# C64-Wifi_UserP.net
KiCad netlist of a schematic drawn in EAGLE
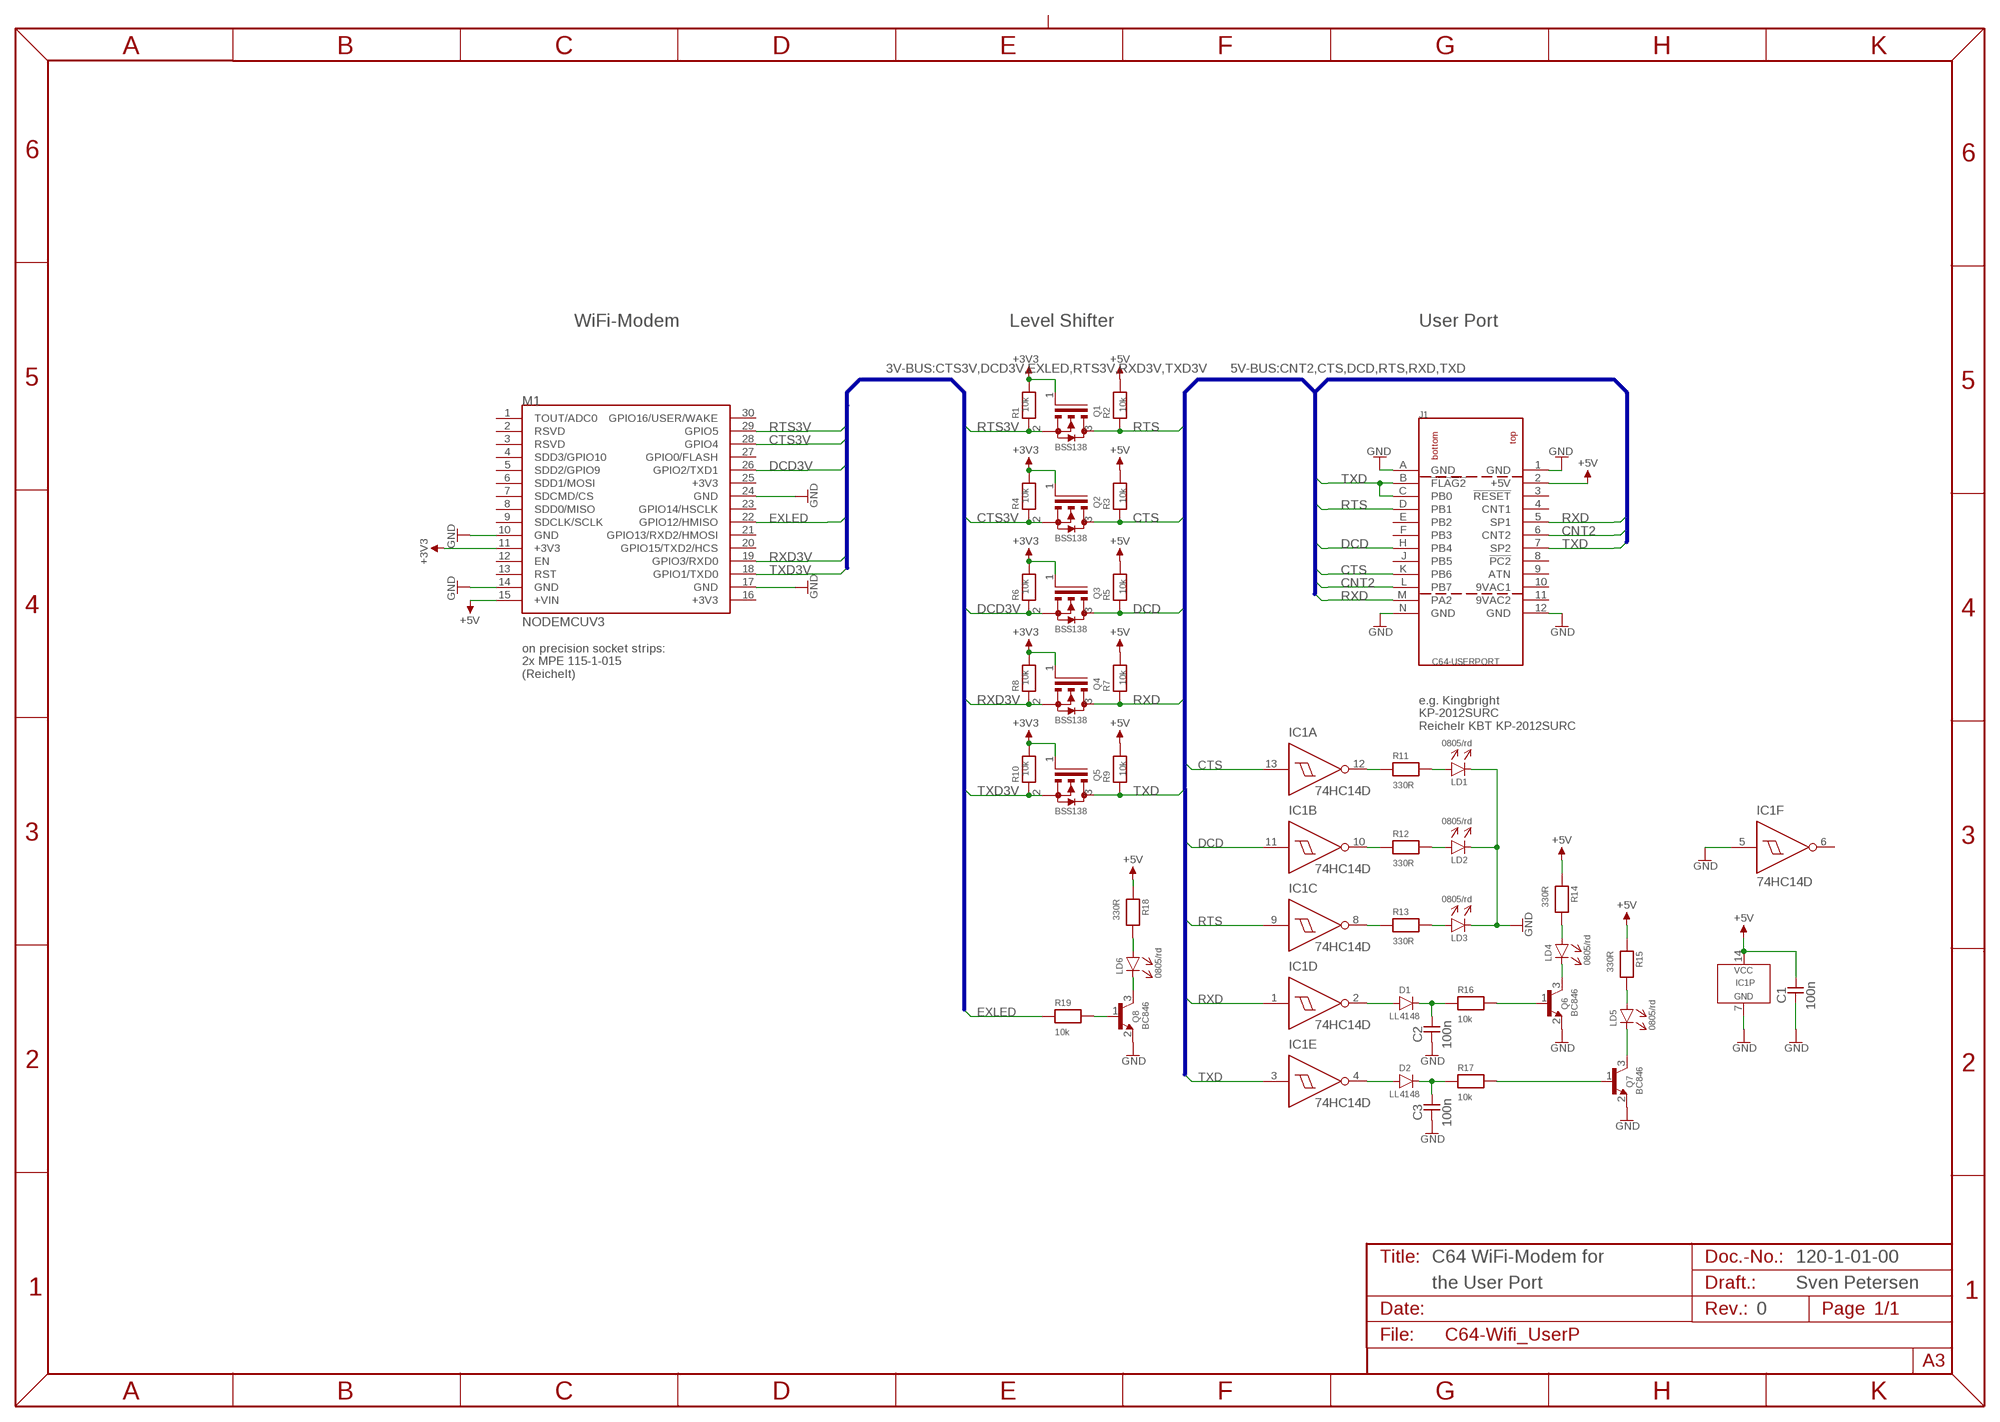
[diagram p0: schematic, sheet 1]

(export (version "E")
  (design (tool "Eeschema 10.0.6"))
  (components
    (comp (ref "C1")
      (value "100n")
      (footprint "eagle-import:0805")
      (libsource (lib "eagle-import") (part "C-0805"))
    )
    (comp (ref "C2")
      (value "100n")
      (footprint "eagle-import:0805")
      (libsource (lib "eagle-import") (part "C-0805"))
    )
    (comp (ref "C3")
      (value "100n")
      (footprint "eagle-import:0805")
      (libsource (lib "eagle-import") (part "C-0805"))
    )
    (comp (ref "D1")
      (value "LL4148")
      (footprint "eagle-import:SOD80C")
      (libsource (lib "eagle-import") (part "LL4148"))
    )
    (comp (ref "D2")
      (value "LL4148")
      (footprint "eagle-import:SOD80C")
      (libsource (lib "eagle-import") (part "LL4148"))
    )
    (comp (ref "IC1")
      (value "74HC14D")
      (footprint "eagle-import:SO-14")
      (libsource (lib "eagle-import") (part "7414"))
    )
    (comp (ref "J1")
      (value "C64-USERPORT")
      (footprint "eagle-import:USERPORT")
      (libsource (lib "eagle-import") (part "C64-USERPORT"))
    )
    (comp (ref "LD1")
      (value "0805/rd")
      (footprint "eagle-import:0805")
      (libsource (lib "eagle-import") (part "0805-LED"))
    )
    (comp (ref "LD2")
      (value "0805/rd")
      (footprint "eagle-import:0805")
      (libsource (lib "eagle-import") (part "0805-LED"))
    )
    (comp (ref "LD3")
      (value "0805/rd")
      (footprint "eagle-import:0805")
      (libsource (lib "eagle-import") (part "0805-LED"))
    )
    (comp (ref "LD4")
      (value "0805/rd")
      (footprint "eagle-import:0805")
      (libsource (lib "eagle-import") (part "0805-LED"))
    )
    (comp (ref "LD5")
      (value "0805/rd")
      (footprint "eagle-import:0805")
      (libsource (lib "eagle-import") (part "0805-LED"))
    )
    (comp (ref "LD6")
      (value "0805/rd")
      (footprint "eagle-import:0805")
      (libsource (lib "eagle-import") (part "0805-LED"))
    )
    (comp (ref "M1")
      (value "NODEMCUV3")
      (footprint "eagle-import:NODEMCUV3")
      (libsource (lib "eagle-import") (part "NODEMCUV3"))
    )
    (comp (ref "Q1")
      (value "BSS138")
      (footprint "eagle-import:SOT23")
      (libsource (lib "eagle-import") (part "BSS138"))
    )
    (comp (ref "Q2")
      (value "BSS138")
      (footprint "eagle-import:SOT23")
      (libsource (lib "eagle-import") (part "BSS138"))
    )
    (comp (ref "Q3")
      (value "BSS138")
      (footprint "eagle-import:SOT23")
      (libsource (lib "eagle-import") (part "BSS138"))
    )
    (comp (ref "Q4")
      (value "BSS138")
      (footprint "eagle-import:SOT23")
      (libsource (lib "eagle-import") (part "BSS138"))
    )
    (comp (ref "Q5")
      (value "BSS138")
      (footprint "eagle-import:SOT23")
      (libsource (lib "eagle-import") (part "BSS138"))
    )
    (comp (ref "Q6")
      (value "BC846")
      (footprint "eagle-import:SOT23")
      (libsource (lib "eagle-import") (part "BC846"))
    )
    (comp (ref "Q7")
      (value "BC846")
      (footprint "eagle-import:SOT23")
      (libsource (lib "eagle-import") (part "BC846"))
    )
    (comp (ref "Q8")
      (value "BC846")
      (footprint "eagle-import:SOT23")
      (libsource (lib "eagle-import") (part "BC846"))
    )
    (comp (ref "R1")
      (value "10k")
      (footprint "eagle-import:0805")
      (libsource (lib "eagle-import") (part "R-0805"))
    )
    (comp (ref "R2")
      (value "10k")
      (footprint "eagle-import:0805")
      (libsource (lib "eagle-import") (part "R-0805"))
    )
    (comp (ref "R3")
      (value "10k")
      (footprint "eagle-import:0805")
      (libsource (lib "eagle-import") (part "R-0805"))
    )
    (comp (ref "R4")
      (value "10k")
      (footprint "eagle-import:0805")
      (libsource (lib "eagle-import") (part "R-0805"))
    )
    (comp (ref "R5")
      (value "10k")
      (footprint "eagle-import:0805")
      (libsource (lib "eagle-import") (part "R-0805"))
    )
    (comp (ref "R6")
      (value "10k")
      (footprint "eagle-import:0805")
      (libsource (lib "eagle-import") (part "R-0805"))
    )
    (comp (ref "R7")
      (value "10k")
      (footprint "eagle-import:0805")
      (libsource (lib "eagle-import") (part "R-0805"))
    )
    (comp (ref "R8")
      (value "10k")
      (footprint "eagle-import:0805")
      (libsource (lib "eagle-import") (part "R-0805"))
    )
    (comp (ref "R9")
      (value "10k")
      (footprint "eagle-import:0805")
      (libsource (lib "eagle-import") (part "R-0805"))
    )
    (comp (ref "R10")
      (value "10k")
      (footprint "eagle-import:0805")
      (libsource (lib "eagle-import") (part "R-0805"))
    )
    (comp (ref "R11")
      (value "330R")
      (footprint "eagle-import:0805")
      (libsource (lib "eagle-import") (part "R-0805"))
    )
    (comp (ref "R12")
      (value "330R")
      (footprint "eagle-import:0805")
      (libsource (lib "eagle-import") (part "R-0805"))
    )
    (comp (ref "R13")
      (value "330R")
      (footprint "eagle-import:0805")
      (libsource (lib "eagle-import") (part "R-0805"))
    )
    (comp (ref "R14")
      (value "330R")
      (footprint "eagle-import:0805")
      (libsource (lib "eagle-import") (part "R-0805"))
    )
    (comp (ref "R15")
      (value "330R")
      (footprint "eagle-import:0805")
      (libsource (lib "eagle-import") (part "R-0805"))
    )
    (comp (ref "R16")
      (value "10k")
      (footprint "eagle-import:0805")
      (libsource (lib "eagle-import") (part "R-0805"))
    )
    (comp (ref "R17")
      (value "10k")
      (footprint "eagle-import:0805")
      (libsource (lib "eagle-import") (part "R-0805"))
    )
    (comp (ref "R18")
      (value "330R")
      (footprint "eagle-import:0805")
      (libsource (lib "eagle-import") (part "R-0805"))
    )
    (comp (ref "R19")
      (value "10k")
      (footprint "eagle-import:0805")
      (libsource (lib "eagle-import") (part "R-0805"))
    )
  )
  (nets
    (net (code "3") (name "+3V3") (class "Default")
      (node (ref "M1") (pin "11") (pinfunction "+3V3_11") (pintype "bidirectional"))
      (node (ref "Q1") (pin "1") (pinfunction "G_1") (pintype "bidirectional"))
      (node (ref "Q2") (pin "1") (pinfunction "G_1") (pintype "bidirectional"))
      (node (ref "Q3") (pin "1") (pinfunction "G_1") (pintype "bidirectional"))
      (node (ref "Q4") (pin "1") (pinfunction "G_1") (pintype "bidirectional"))
      (node (ref "Q5") (pin "1") (pinfunction "G_1") (pintype "bidirectional"))
      (node (ref "R1") (pin "2") (pinfunction "2_2") (pintype "passive"))
      (node (ref "R10") (pin "2") (pinfunction "2_2") (pintype "passive"))
      (node (ref "R4") (pin "2") (pinfunction "2_2") (pintype "passive"))
      (node (ref "R6") (pin "2") (pinfunction "2_2") (pintype "passive"))
      (node (ref "R8") (pin "2") (pinfunction "2_2") (pintype "passive"))
    )
    (net (code "4") (name "+5V") (class "Default")
      (node (ref "C1") (pin "2") (pinfunction "2_2") (pintype "passive"))
      (node (ref "IC1") (pin "14") (pinfunction "VCC_14") (pintype "bidirectional"))
      (node (ref "J1") (pin "2") (pinfunction "+5V_2") (pintype "power_in"))
      (node (ref "M1") (pin "15") (pinfunction "+VIN_15") (pintype "bidirectional"))
      (node (ref "R14") (pin "1") (pinfunction "1_1") (pintype "passive"))
      (node (ref "R15") (pin "1") (pinfunction "1_1") (pintype "passive"))
      (node (ref "R18") (pin "1") (pinfunction "1_1") (pintype "passive"))
      (node (ref "R2") (pin "2") (pinfunction "2_2") (pintype "passive"))
      (node (ref "R3") (pin "2") (pinfunction "2_2") (pintype "passive"))
      (node (ref "R5") (pin "2") (pinfunction "2_2") (pintype "passive"))
      (node (ref "R7") (pin "2") (pinfunction "2_2") (pintype "passive"))
      (node (ref "R9") (pin "2") (pinfunction "2_2") (pintype "passive"))
    )
    (net (code "5") (name "/9VAC1") (class "Default")
      (node (ref "J1") (pin "10") (pinfunction "9VAC1_10") (pintype "power_in"))
    )
    (net (code "6") (name "/9VAC2") (class "Default")
      (node (ref "J1") (pin "11") (pinfunction "9VAC2_11") (pintype "power_in"))
    )
    (net (code "7") (name "/CNT2") (class "Default")
      (node (ref "J1") (pin "6") (pinfunction "CNT2_6") (pintype "input"))
      (node (ref "J1") (pin "L") (pinfunction "PB7_L") (pintype "bidirectional"))
    )
    (net (code "8") (name "/CTS") (class "Default")
      (node (ref "IC1") (pin "13") (pinfunction "I_13") (pintype "input"))
      (node (ref "J1") (pin "K") (pinfunction "PB6_K") (pintype "bidirectional"))
      (node (ref "Q2") (pin "3") (pinfunction "D_3") (pintype "bidirectional"))
      (node (ref "R3") (pin "1") (pinfunction "1_1") (pintype "passive"))
    )
    (net (code "9") (name "/CTS3V") (class "Default")
      (node (ref "M1") (pin "28") (pinfunction "GPIO4_28") (pintype "bidirectional"))
      (node (ref "Q2") (pin "2") (pinfunction "S_2") (pintype "bidirectional"))
      (node (ref "R4") (pin "1") (pinfunction "1_1") (pintype "passive"))
    )
    (net (code "10") (name "/DCD") (class "Default")
      (node (ref "IC1") (pin "11") (pinfunction "I_11") (pintype "input"))
      (node (ref "J1") (pin "H") (pinfunction "PB4_H") (pintype "bidirectional"))
      (node (ref "Q3") (pin "3") (pinfunction "D_3") (pintype "bidirectional"))
      (node (ref "R5") (pin "1") (pinfunction "1_1") (pintype "passive"))
    )
    (net (code "11") (name "/DCD3V") (class "Default")
      (node (ref "M1") (pin "26") (pinfunction "GPIO2/TXD1_26") (pintype "bidirectional"))
      (node (ref "Q3") (pin "2") (pinfunction "S_2") (pintype "bidirectional"))
      (node (ref "R6") (pin "1") (pinfunction "1_1") (pintype "passive"))
    )
    (net (code "12") (name "/EXLED") (class "Default")
      (node (ref "M1") (pin "22") (pinfunction "GPIO12/HMISO_22") (pintype "bidirectional"))
      (node (ref "R19") (pin "1") (pinfunction "1_1") (pintype "passive"))
    )
    (net (code "13") (name "/RTS") (class "Default")
      (node (ref "IC1") (pin "9") (pinfunction "I_9") (pintype "input"))
      (node (ref "J1") (pin "D") (pinfunction "PB1_D") (pintype "bidirectional"))
      (node (ref "Q1") (pin "3") (pinfunction "D_3") (pintype "bidirectional"))
      (node (ref "R2") (pin "1") (pinfunction "1_1") (pintype "passive"))
    )
    (net (code "14") (name "/RTS3V") (class "Default")
      (node (ref "M1") (pin "29") (pinfunction "GPIO5_29") (pintype "bidirectional"))
      (node (ref "Q1") (pin "2") (pinfunction "S_2") (pintype "bidirectional"))
      (node (ref "R1") (pin "1") (pinfunction "1_1") (pintype "passive"))
    )
    (net (code "15") (name "/RXD") (class "Default")
      (node (ref "IC1") (pin "1") (pinfunction "I_1") (pintype "input"))
      (node (ref "J1") (pin "5") (pinfunction "SP1_5") (pintype "bidirectional"))
      (node (ref "J1") (pin "M") (pinfunction "PA2_M") (pintype "bidirectional"))
      (node (ref "Q4") (pin "3") (pinfunction "D_3") (pintype "bidirectional"))
      (node (ref "R7") (pin "1") (pinfunction "1_1") (pintype "passive"))
    )
    (net (code "16") (name "/RXD3V") (class "Default")
      (node (ref "M1") (pin "19") (pinfunction "GPIO3/RXD0_19") (pintype "bidirectional"))
      (node (ref "Q4") (pin "2") (pinfunction "S_2") (pintype "bidirectional"))
      (node (ref "R8") (pin "1") (pinfunction "1_1") (pintype "passive"))
    )
    (net (code "17") (name "/TXD") (class "Default")
      (node (ref "IC1") (pin "3") (pinfunction "I_3") (pintype "input"))
      (node (ref "J1") (pin "7") (pinfunction "SP2_7") (pintype "bidirectional"))
      (node (ref "J1") (pin "B") (pinfunction "~{FLAG2}_B") (pintype "input"))
      (node (ref "J1") (pin "C") (pinfunction "PB0_C") (pintype "bidirectional"))
      (node (ref "Q5") (pin "3") (pinfunction "D_3") (pintype "bidirectional"))
      (node (ref "R9") (pin "1") (pinfunction "1_1") (pintype "passive"))
    )
    (net (code "18") (name "/TXD3V") (class "Default")
      (node (ref "M1") (pin "18") (pinfunction "GPIO1/TXD0_18") (pintype "bidirectional"))
      (node (ref "Q5") (pin "2") (pinfunction "S_2") (pintype "bidirectional"))
      (node (ref "R10") (pin "1") (pinfunction "1_1") (pintype "passive"))
    )
    (net (code "21") (name "GND") (class "Default")
      (node (ref "C1") (pin "1") (pinfunction "1_1") (pintype "passive"))
      (node (ref "C2") (pin "1") (pinfunction "1_1") (pintype "passive"))
      (node (ref "C3") (pin "1") (pinfunction "1_1") (pintype "passive"))
      (node (ref "IC1") (pin "5") (pinfunction "I_5") (pintype "input"))
      (node (ref "IC1") (pin "7") (pinfunction "GND_7") (pintype "bidirectional"))
      (node (ref "J1") (pin "1") (pinfunction "GND_1") (pintype "power_in"))
      (node (ref "J1") (pin "12") (pinfunction "GND_12") (pintype "power_in"))
      (node (ref "J1") (pin "A") (pinfunction "GND_A") (pintype "power_in"))
      (node (ref "J1") (pin "N") (pinfunction "GND_N") (pintype "power_in"))
      (node (ref "LD1") (pin "K") (pinfunction "K_K") (pintype "bidirectional"))
      (node (ref "LD2") (pin "K") (pinfunction "K_K") (pintype "bidirectional"))
      (node (ref "LD3") (pin "K") (pinfunction "K_K") (pintype "bidirectional"))
      (node (ref "M1") (pin "10") (pinfunction "GND_10") (pintype "bidirectional"))
      (node (ref "M1") (pin "14") (pinfunction "GND_14") (pintype "bidirectional"))
      (node (ref "M1") (pin "17") (pinfunction "GND_17") (pintype "bidirectional"))
      (node (ref "M1") (pin "24") (pinfunction "GND_24") (pintype "bidirectional"))
      (node (ref "Q6") (pin "2") (pinfunction "E_2") (pintype "passive"))
      (node (ref "Q7") (pin "2") (pinfunction "E_2") (pintype "passive"))
      (node (ref "Q8") (pin "2") (pinfunction "E_2") (pintype "passive"))
    )
    (net (code "22") (name "Net-(C2-Pad2)") (class "Default")
      (node (ref "C2") (pin "2") (pinfunction "2_2") (pintype "passive"))
      (node (ref "D1") (pin "K") (pinfunction "K_K") (pintype "passive"))
      (node (ref "R16") (pin "1") (pinfunction "1_1") (pintype "passive"))
    )
    (net (code "23") (name "Net-(C3-Pad2)") (class "Default")
      (node (ref "C3") (pin "2") (pinfunction "2_2") (pintype "passive"))
      (node (ref "D2") (pin "K") (pinfunction "K_K") (pintype "passive"))
      (node (ref "R17") (pin "1") (pinfunction "1_1") (pintype "passive"))
    )
    (net (code "24") (name "Net-(IC1A-O)") (class "Default")
      (node (ref "IC1") (pin "12") (pinfunction "O_12") (pintype "output"))
      (node (ref "R11") (pin "1") (pinfunction "1_1") (pintype "passive"))
    )
    (net (code "25") (name "Net-(IC1B-O)") (class "Default")
      (node (ref "IC1") (pin "10") (pinfunction "O_10") (pintype "output"))
      (node (ref "R12") (pin "1") (pinfunction "1_1") (pintype "passive"))
    )
    (net (code "26") (name "Net-(IC1C-O)") (class "Default")
      (node (ref "IC1") (pin "8") (pinfunction "O_8") (pintype "output"))
      (node (ref "R13") (pin "1") (pinfunction "1_1") (pintype "passive"))
    )
    (net (code "27") (name "Net-(IC1D-O)") (class "Default")
      (node (ref "D1") (pin "A") (pinfunction "A_A") (pintype "passive"))
      (node (ref "IC1") (pin "2") (pinfunction "O_2") (pintype "output"))
    )
    (net (code "28") (name "Net-(IC1E-O)") (class "Default")
      (node (ref "D2") (pin "A") (pinfunction "A_A") (pintype "passive"))
      (node (ref "IC1") (pin "4") (pinfunction "O_4") (pintype "output"))
    )
    (net (code "29") (name "Net-(LD1-PadA)") (class "Default")
      (node (ref "LD1") (pin "A") (pinfunction "A_A") (pintype "bidirectional"))
      (node (ref "R11") (pin "2") (pinfunction "2_2") (pintype "passive"))
    )
    (net (code "30") (name "Net-(LD2-PadA)") (class "Default")
      (node (ref "LD2") (pin "A") (pinfunction "A_A") (pintype "bidirectional"))
      (node (ref "R12") (pin "2") (pinfunction "2_2") (pintype "passive"))
    )
    (net (code "31") (name "Net-(LD3-PadA)") (class "Default")
      (node (ref "LD3") (pin "A") (pinfunction "A_A") (pintype "bidirectional"))
      (node (ref "R13") (pin "2") (pinfunction "2_2") (pintype "passive"))
    )
    (net (code "32") (name "Net-(LD4-PadA)") (class "Default")
      (node (ref "LD4") (pin "A") (pinfunction "A_A") (pintype "bidirectional"))
      (node (ref "R14") (pin "2") (pinfunction "2_2") (pintype "passive"))
    )
    (net (code "33") (name "Net-(LD5-PadA)") (class "Default")
      (node (ref "LD5") (pin "A") (pinfunction "A_A") (pintype "bidirectional"))
      (node (ref "R15") (pin "2") (pinfunction "2_2") (pintype "passive"))
    )
    (net (code "34") (name "Net-(LD6-PadA)") (class "Default")
      (node (ref "LD6") (pin "A") (pinfunction "A_A") (pintype "bidirectional"))
      (node (ref "R18") (pin "2") (pinfunction "2_2") (pintype "passive"))
    )
    (net (code "35") (name "Net-(Q6-B)") (class "Default")
      (node (ref "Q6") (pin "1") (pinfunction "B_1") (pintype "passive"))
      (node (ref "R16") (pin "2") (pinfunction "2_2") (pintype "passive"))
    )
    (net (code "36") (name "Net-(Q6-C)") (class "Default")
      (node (ref "LD4") (pin "K") (pinfunction "K_K") (pintype "bidirectional"))
      (node (ref "Q6") (pin "3") (pinfunction "C_3") (pintype "passive"))
    )
    (net (code "37") (name "Net-(Q7-B)") (class "Default")
      (node (ref "Q7") (pin "1") (pinfunction "B_1") (pintype "passive"))
      (node (ref "R17") (pin "2") (pinfunction "2_2") (pintype "passive"))
    )
    (net (code "38") (name "Net-(Q7-C)") (class "Default")
      (node (ref "LD5") (pin "K") (pinfunction "K_K") (pintype "bidirectional"))
      (node (ref "Q7") (pin "3") (pinfunction "C_3") (pintype "passive"))
    )
    (net (code "39") (name "Net-(Q8-B)") (class "Default")
      (node (ref "Q8") (pin "1") (pinfunction "B_1") (pintype "passive"))
      (node (ref "R19") (pin "2") (pinfunction "2_2") (pintype "passive"))
    )
    (net (code "40") (name "Net-(Q8-C)") (class "Default")
      (node (ref "LD6") (pin "K") (pinfunction "K_K") (pintype "bidirectional"))
      (node (ref "Q8") (pin "3") (pinfunction "C_3") (pintype "passive"))
    )
    (net (code "41") (name "unconnected-(IC1F-O-Pad6)") (class "Default")
      (node (ref "IC1") (pin "6") (pinfunction "O_6") (pintype "output"))
    )
    (net (code "42") (name "unconnected-(J1-ATN-Pad9)") (class "Default")
      (node (ref "J1") (pin "9") (pinfunction "ATN_9") (pintype "bidirectional"))
    )
    (net (code "43") (name "unconnected-(J1-CNT1-Pad4)") (class "Default")
      (node (ref "J1") (pin "4") (pinfunction "CNT1_4") (pintype "input"))
    )
    (net (code "44") (name "unconnected-(J1-PB2-PadE)") (class "Default")
      (node (ref "J1") (pin "E") (pinfunction "PB2_E") (pintype "bidirectional"))
    )
    (net (code "45") (name "unconnected-(J1-PB3-PadF)") (class "Default")
      (node (ref "J1") (pin "F") (pinfunction "PB3_F") (pintype "bidirectional"))
    )
    (net (code "46") (name "unconnected-(J1-PB5-PadJ)") (class "Default")
      (node (ref "J1") (pin "J") (pinfunction "PB5_J") (pintype "bidirectional"))
    )
    (net (code "47") (name "unconnected-(J1-~{PC2}-Pad8)") (class "Default")
      (node (ref "J1") (pin "8") (pinfunction "~{PC2}_8") (pintype "bidirectional"))
    )
    (net (code "48") (name "unconnected-(J1-~{RESET}-Pad3)") (class "Default")
      (node (ref "J1") (pin "3") (pinfunction "~{RESET}_3") (pintype "bidirectional"))
    )
    (net (code "49") (name "unconnected-(M1-+3V3-Pad16)") (class "Default")
      (node (ref "M1") (pin "16") (pinfunction "+3V3_16") (pintype "bidirectional"))
    )
    (net (code "50") (name "unconnected-(M1-+3V3-Pad25)") (class "Default")
      (node (ref "M1") (pin "25") (pinfunction "+3V3_25") (pintype "bidirectional"))
    )
    (net (code "51") (name "unconnected-(M1-EN-Pad12)") (class "Default")
      (node (ref "M1") (pin "12") (pinfunction "EN_12") (pintype "bidirectional"))
    )
    (net (code "52") (name "unconnected-(M1-GPIO0{slash}FLASH-Pad27)") (class "Default")
      (node (ref "M1") (pin "27") (pinfunction "GPIO0/FLASH_27") (pintype "bidirectional"))
    )
    (net (code "53") (name "unconnected-(M1-GPIO13{slash}RXD2{slash}HMOSI-Pad21)") (class "Default")
      (node (ref "M1") (pin "21") (pinfunction "GPIO13/RXD2/HMOSI_21") (pintype "bidirectional"))
    )
    (net (code "54") (name "unconnected-(M1-GPIO14{slash}HSCLK-Pad23)") (class "Default")
      (node (ref "M1") (pin "23") (pinfunction "GPIO14/HSCLK_23") (pintype "bidirectional"))
    )
    (net (code "55") (name "unconnected-(M1-GPIO15{slash}TXD2{slash}HCS-Pad20)") (class "Default")
      (node (ref "M1") (pin "20") (pinfunction "GPIO15/TXD2/HCS_20") (pintype "bidirectional"))
    )
    (net (code "56") (name "unconnected-(M1-GPIO16{slash}USER{slash}WAKE-Pad30)") (class "Default")
      (node (ref "M1") (pin "30") (pinfunction "GPIO16/USER/WAKE_30") (pintype "bidirectional"))
    )
    (net (code "57") (name "unconnected-(M1-RST-Pad13)") (class "Default")
      (node (ref "M1") (pin "13") (pinfunction "RST_13") (pintype "bidirectional"))
    )
    (net (code "58") (name "unconnected-(M1-RSVD-Pad2)") (class "Default")
      (node (ref "M1") (pin "2") (pinfunction "RSVD_2") (pintype "bidirectional"))
    )
    (net (code "59") (name "unconnected-(M1-RSVD-Pad3)") (class "Default")
      (node (ref "M1") (pin "3") (pinfunction "RSVD_3") (pintype "bidirectional"))
    )
    (net (code "60") (name "unconnected-(M1-SDCLK{slash}SCLK-Pad9)") (class "Default")
      (node (ref "M1") (pin "9") (pinfunction "SDCLK/SCLK_9") (pintype "bidirectional"))
    )
    (net (code "61") (name "unconnected-(M1-SDCMD{slash}CS-Pad7)") (class "Default")
      (node (ref "M1") (pin "7") (pinfunction "SDCMD/CS_7") (pintype "bidirectional"))
    )
    (net (code "62") (name "unconnected-(M1-SDD0{slash}MISO-Pad8)") (class "Default")
      (node (ref "M1") (pin "8") (pinfunction "SDD0/MISO_8") (pintype "bidirectional"))
    )
    (net (code "63") (name "unconnected-(M1-SDD1{slash}MOSI-Pad6)") (class "Default")
      (node (ref "M1") (pin "6") (pinfunction "SDD1/MOSI_6") (pintype "bidirectional"))
    )
    (net (code "64") (name "unconnected-(M1-SDD2{slash}GPIO9-Pad5)") (class "Default")
      (node (ref "M1") (pin "5") (pinfunction "SDD2/GPIO9_5") (pintype "bidirectional"))
    )
    (net (code "65") (name "unconnected-(M1-SDD3{slash}GPIO10-Pad4)") (class "Default")
      (node (ref "M1") (pin "4") (pinfunction "SDD3/GPIO10_4") (pintype "bidirectional"))
    )
    (net (code "66") (name "unconnected-(M1-TOUT{slash}ADC0-Pad1)") (class "Default")
      (node (ref "M1") (pin "1") (pinfunction "TOUT/ADC0_1") (pintype "bidirectional"))
    )
  )
)
